# 15_IO_USB.net
KiCad netlist of a schematic drawn in Altium Designer
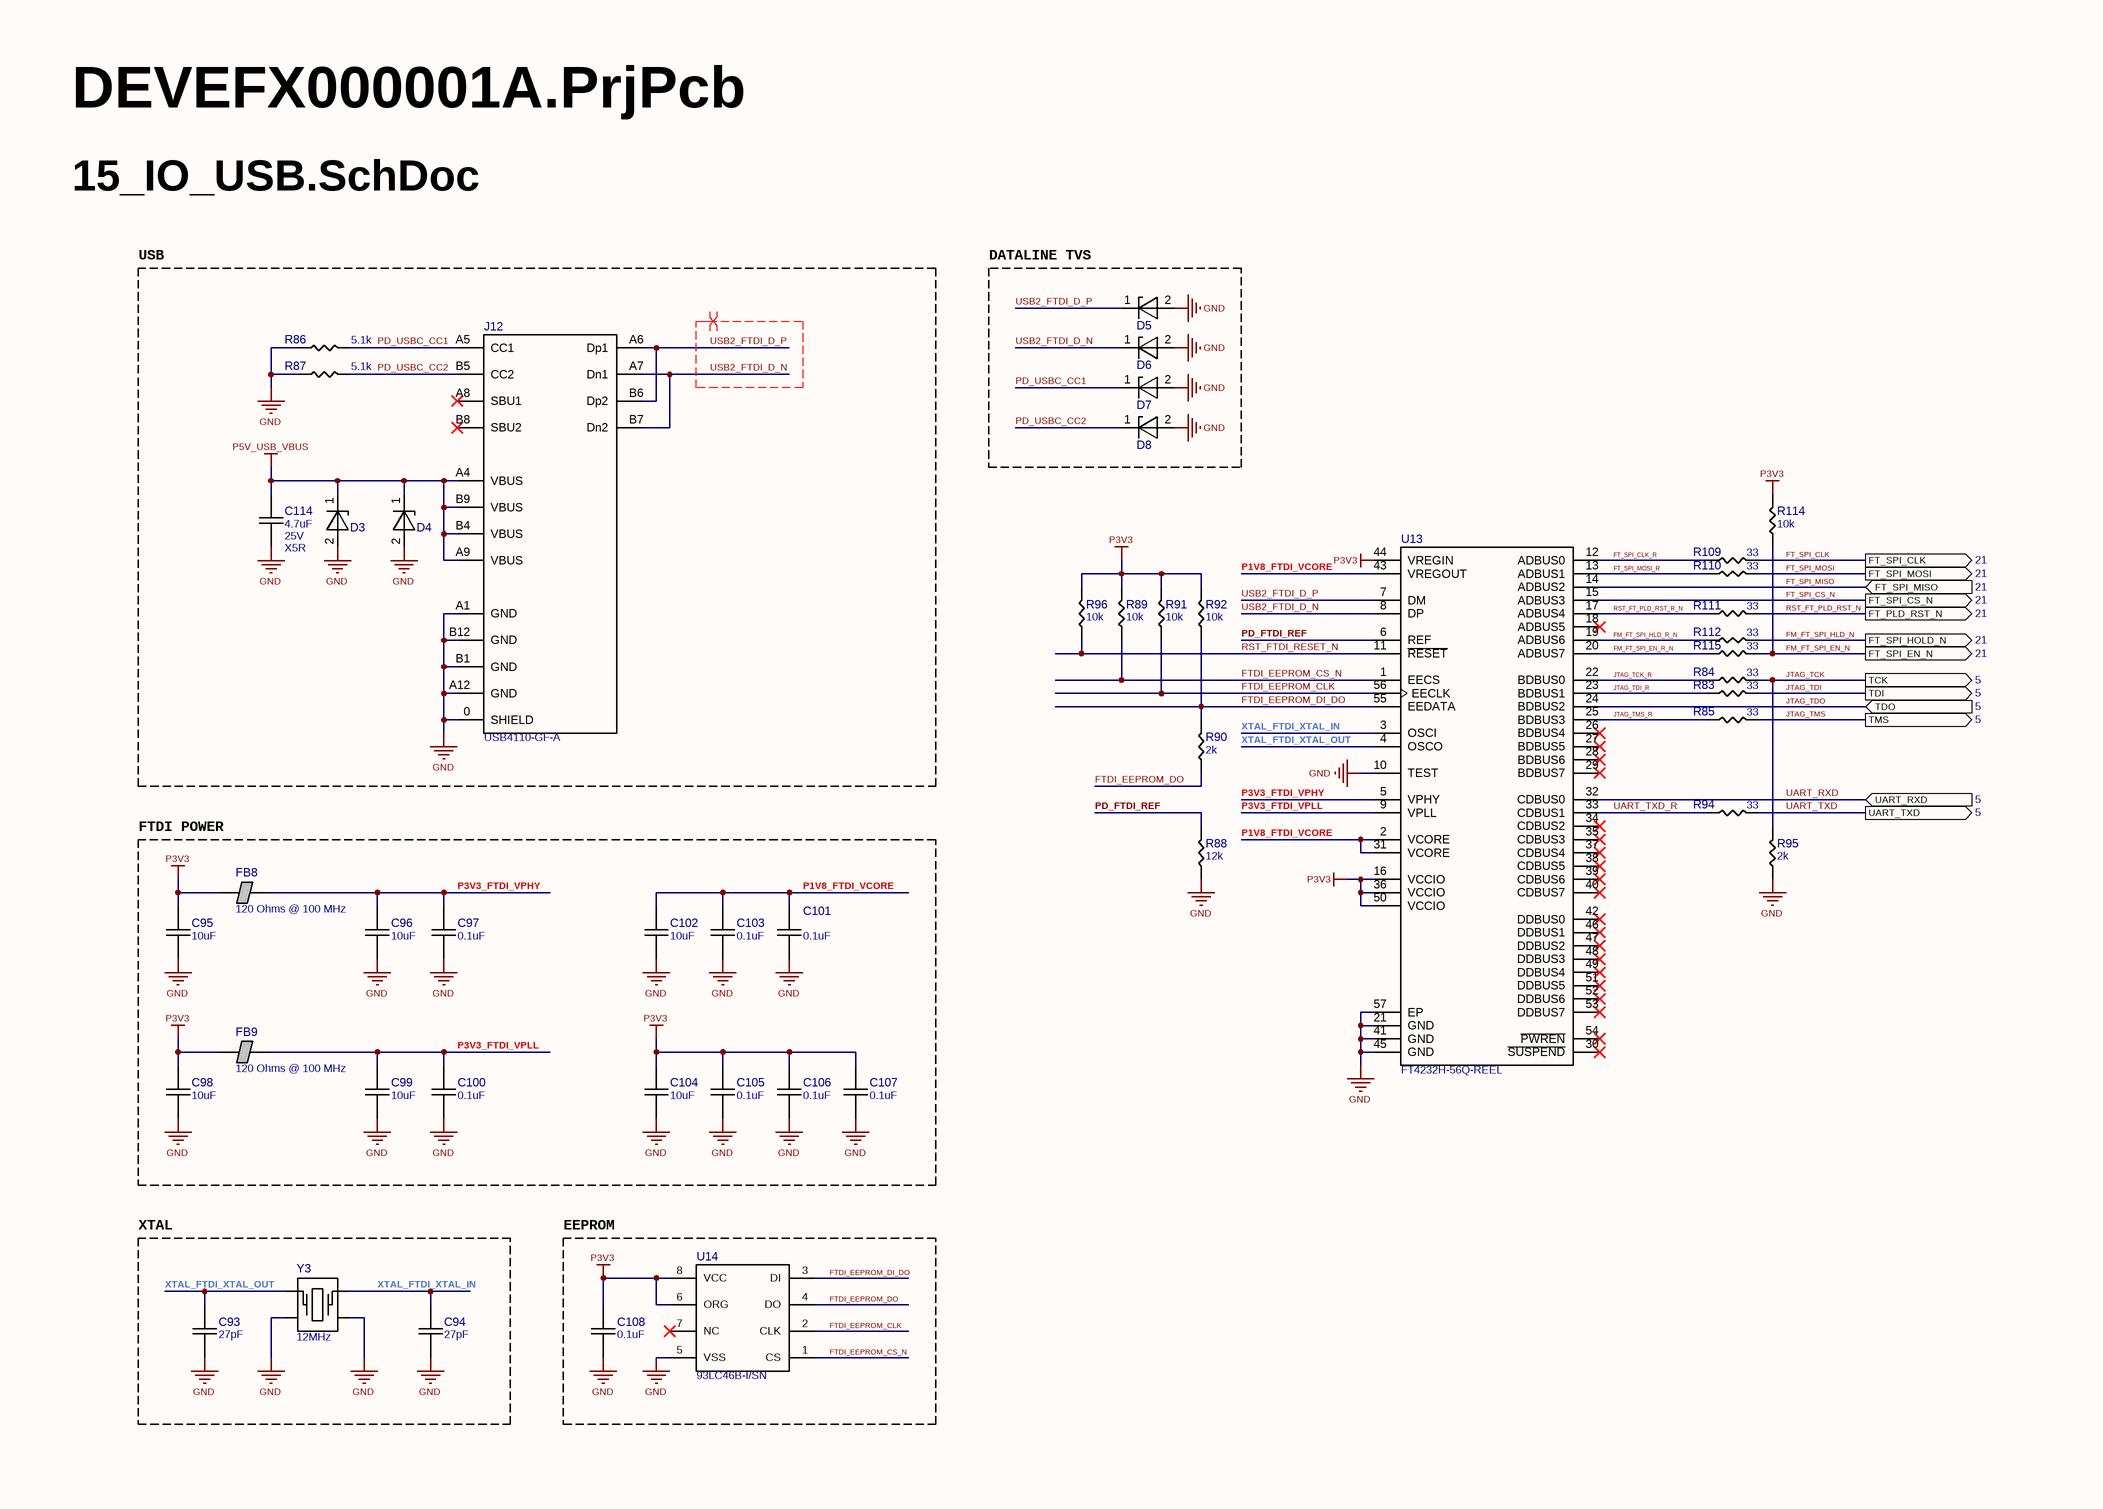
[diagram p0: 15_IO_USB.SchDoc]

(export (version "E")
  (design (tool "Eeschema 10.0.6"))
  (components
    (comp (ref "C93")
      (value "27pF")
      (footprint "CAPC1005X06N")
      (description "CAP CER 27PF 50V C0G/NPO 0402")
      (fields (field (name "PART NUMBER") "CC0402JRNPO9BN270") (field (name "VOLTAGE") "50V"))
      (libsource (lib "Database") (part "Capacitor"))
    )
    (comp (ref "C94")
      (value "27pF")
      (footprint "CAPC1005X06N")
      (description "CAP CER 27PF 50V C0G/NPO 0402")
      (fields (field (name "PART NUMBER") "CC0402JRNPO9BN270") (field (name "VOLTAGE") "50V"))
      (libsource (lib "Database") (part "Capacitor"))
    )
    (comp (ref "C95")
      (value "10uF")
      (footprint "CAPC1005X06N")
      (description "CAP CER 10UF 6.3V X5R 0402")
      (fields (field (name "PART NUMBER") "GRM155R60J106ME47D") (field (name "VOLTAGE") "6.3V"))
      (libsource (lib "Database") (part "Capacitor"))
    )
    (comp (ref "C96")
      (value "10uF")
      (footprint "CAPC1005X06N")
      (description "CAP CER 10UF 6.3V X5R 0402")
      (fields (field (name "PART NUMBER") "GRM155R60J106ME47D") (field (name "VOLTAGE") "6.3V"))
      (libsource (lib "Database") (part "Capacitor"))
    )
    (comp (ref "C97")
      (value "0.1uF")
      (footprint "CAPC1005X06N")
      (description "CAP CER 0.1UF 25V X7R 0402")
      (fields (field (name "PART NUMBER") "GRM155R71E104KE14J") (field (name "VOLTAGE") "25V"))
      (libsource (lib "Database") (part "Capacitor"))
    )
    (comp (ref "C98")
      (value "10uF")
      (footprint "CAPC1005X06N")
      (description "CAP CER 10UF 6.3V X5R 0402")
      (fields (field (name "PART NUMBER") "GRM155R60J106ME47D") (field (name "VOLTAGE") "6.3V"))
      (libsource (lib "Database") (part "Capacitor"))
    )
    (comp (ref "C99")
      (value "10uF")
      (footprint "CAPC1005X06N")
      (description "CAP CER 10UF 6.3V X5R 0402")
      (fields (field (name "PART NUMBER") "GRM155R60J106ME47D") (field (name "VOLTAGE") "6.3V"))
      (libsource (lib "Database") (part "Capacitor"))
    )
    (comp (ref "C100")
      (value "0.1uF")
      (footprint "CAPC1005X06N")
      (description "CAP CER 0.1UF 25V X7R 0402")
      (fields (field (name "PART NUMBER") "GRM155R71E104KE14J") (field (name "VOLTAGE") "25V"))
      (libsource (lib "Database") (part "Capacitor"))
    )
    (comp (ref "C101")
      (value "0.1uF")
      (footprint "CAPC1005X06N")
      (description "CAP CER 0.1UF 25V X7R 0402")
      (fields (field (name "PART NUMBER") "GRM155R71E104KE14J") (field (name "VOLTAGE") "25V"))
      (libsource (lib "Database") (part "Capacitor"))
    )
    (comp (ref "C102")
      (value "10uF")
      (footprint "CAPC1005X06N")
      (description "CAP CER 10UF 6.3V X5R 0402")
      (fields (field (name "PART NUMBER") "GRM155R60J106ME47D") (field (name "VOLTAGE") "6.3V"))
      (libsource (lib "Database") (part "Capacitor"))
    )
    (comp (ref "C103")
      (value "0.1uF")
      (footprint "CAPC1005X06N")
      (description "CAP CER 0.1UF 25V X7R 0402")
      (fields (field (name "PART NUMBER") "GRM155R71E104KE14J") (field (name "VOLTAGE") "25V"))
      (libsource (lib "Database") (part "Capacitor"))
    )
    (comp (ref "C104")
      (value "10uF")
      (footprint "CAPC1005X06N")
      (description "CAP CER 10UF 6.3V X5R 0402")
      (fields (field (name "PART NUMBER") "GRM155R60J106ME47D") (field (name "VOLTAGE") "6.3V"))
      (libsource (lib "Database") (part "Capacitor"))
    )
    (comp (ref "C105")
      (value "0.1uF")
      (footprint "CAPC1005X06N")
      (description "CAP CER 0.1UF 25V X7R 0402")
      (fields (field (name "PART NUMBER") "GRM155R71E104KE14J") (field (name "VOLTAGE") "25V"))
      (libsource (lib "Database") (part "Capacitor"))
    )
    (comp (ref "C106")
      (value "0.1uF")
      (footprint "CAPC1005X06N")
      (description "CAP CER 0.1UF 25V X7R 0402")
      (fields (field (name "PART NUMBER") "GRM155R71E104KE14J") (field (name "VOLTAGE") "25V"))
      (libsource (lib "Database") (part "Capacitor"))
    )
    (comp (ref "C107")
      (value "0.1uF")
      (footprint "CAPC1005X06N")
      (description "CAP CER 0.1UF 25V X7R 0402")
      (fields (field (name "PART NUMBER") "GRM155R71E104KE14J") (field (name "VOLTAGE") "25V"))
      (libsource (lib "Database") (part "Capacitor"))
    )
    (comp (ref "C108")
      (value "0.1uF")
      (footprint "CAPC1005X06N")
      (description "CAP CER 0.1UF 25V X7R 0402")
      (fields (field (name "PART NUMBER") "GRM155R71E104KE14J") (field (name "VOLTAGE") "25V"))
      (libsource (lib "Database") (part "Capacitor"))
    )
    (comp (ref "C114")
      (value "4.7uF")
      (footprint "CAPC1608X08N")
      (description "CAP CER 4.7UF 25V X5R 0603")
      (fields
        (field (name "PART NUMBER") "GRM188R61E475KE11D")
        (field (name "VOLTAGE") "25V")
        (field (name "TEMPC") "X5R")
      )
      (libsource (lib "Database") (part "Capacitor"))
    )
    (comp (ref "D3")
      (value "ESD401DPYR")
      (footprint "DFN65P100X50-2N")
      (description "TVS DIODE 5.5V 24V 2X1SON")
      (libsource (lib "Database") (part "Diode Zener"))
    )
    (comp (ref "D4")
      (value "ESD401DPYR")
      (footprint "DFN65P100X50-2N")
      (description "TVS DIODE 5.5V 24V 2X1SON")
      (libsource (lib "Database") (part "Diode Zener"))
    )
    (comp (ref "D5")
      (value "ESD401DPYR")
      (footprint "DFN65P100X50-2N")
      (description "TVS DIODE 5.5V 24V 2X1SON")
      (libsource (lib "Database") (part "Diode Zener"))
    )
    (comp (ref "D6")
      (value "ESD401DPYR")
      (footprint "DFN65P100X50-2N")
      (description "TVS DIODE 5.5V 24V 2X1SON")
      (libsource (lib "Database") (part "Diode Zener"))
    )
    (comp (ref "D7")
      (value "ESD401DPYR")
      (footprint "DFN65P100X50-2N")
      (description "TVS DIODE 5.5V 24V 2X1SON")
      (libsource (lib "Database") (part "Diode Zener"))
    )
    (comp (ref "D8")
      (value "ESD401DPYR")
      (footprint "DFN65P100X50-2N")
      (description "TVS DIODE 5.5V 24V 2X1SON")
      (libsource (lib "Database") (part "Diode Zener"))
    )
    (comp (ref "FB8")
      (value "120 Ohms @ 100 MHz")
      (footprint "INDC1005X05N")
      (description "FERRITE BEAD 120 OHM 0402 1LN")
      (fields (field (name "PART NUMBER") "BLM15PD121SN1D"))
      (libsource (lib "Database") (part "Bead"))
    )
    (comp (ref "FB9")
      (value "120 Ohms @ 100 MHz")
      (footprint "INDC1005X05N")
      (description "FERRITE BEAD 120 OHM 0402 1LN")
      (fields (field (name "PART NUMBER") "BLM15PD121SN1D"))
      (libsource (lib "Database") (part "Bead"))
    )
    (comp (ref "J12")
      (value "USB4110-GF-A")
      (footprint "GCT_USB4110-GF-A")
      (description "CONN RCP USB2.0 TYP C 24P SMD RA")
      (libsource (lib "Database") (part "Connector Type-C USB2"))
    )
    (comp (ref "R83")
      (value "33")
      (footprint "RESC1005X03N")
      (description "RES SMD 33 OHM 1% 1/16W 0402")
      (fields (field (name "PART NUMBER") "RC0402FR-0733RL"))
      (libsource (lib "Database") (part "Resistor_ENG"))
    )
    (comp (ref "R84")
      (value "33")
      (footprint "RESC1005X03N")
      (description "RES SMD 33 OHM 1% 1/16W 0402")
      (fields (field (name "PART NUMBER") "RC0402FR-0733RL"))
      (libsource (lib "Database") (part "Resistor_ENG"))
    )
    (comp (ref "R85")
      (value "33")
      (footprint "RESC1005X03N")
      (description "RES SMD 33 OHM 1% 1/16W 0402")
      (fields (field (name "PART NUMBER") "RC0402FR-0733RL"))
      (libsource (lib "Database") (part "Resistor_ENG"))
    )
    (comp (ref "R86")
      (value "5.1k")
      (footprint "RESC1005X03N")
      (description "RES SMD 5.1K OHM 1% 1/16W 0402")
      (fields (field (name "PART NUMBER") "RC0402FR-075K1L"))
      (libsource (lib "Database") (part "Resistor_ENG"))
    )
    (comp (ref "R87")
      (value "5.1k")
      (footprint "RESC1005X03N")
      (description "RES SMD 5.1K OHM 1% 1/16W 0402")
      (fields (field (name "PART NUMBER") "RC0402FR-075K1L"))
      (libsource (lib "Database") (part "Resistor_ENG"))
    )
    (comp (ref "R88")
      (value "12k")
      (footprint "RESC1005X03N")
      (description "RES SMD 12K OHM 1% 1/16W 0402")
      (fields (field (name "PART NUMBER") "RC0402FR-0712KL"))
      (libsource (lib "Database") (part "Resistor_ENG"))
    )
    (comp (ref "R89")
      (value "10k")
      (footprint "RESC1005X03N")
      (description "RES SMD 10K OHM 1% 1/16W 0402")
      (fields (field (name "PART NUMBER") "RC0402FR-0710KL"))
      (libsource (lib "Database") (part "Resistor_ENG"))
    )
    (comp (ref "R90")
      (value "2k")
      (footprint "RESC1005X03N")
      (description "RES SMD 2K OHM 1% 1/16W 0402")
      (fields (field (name "PART NUMBER") "RC0402FR-072KL"))
      (libsource (lib "Database") (part "Resistor_ENG"))
    )
    (comp (ref "R91")
      (value "10k")
      (footprint "RESC1005X03N")
      (description "RES SMD 10K OHM 1% 1/16W 0402")
      (fields (field (name "PART NUMBER") "RC0402FR-0710KL"))
      (libsource (lib "Database") (part "Resistor_ENG"))
    )
    (comp (ref "R92")
      (value "10k")
      (footprint "RESC1005X03N")
      (description "RES SMD 10K OHM 1% 1/16W 0402")
      (fields (field (name "PART NUMBER") "RC0402FR-0710KL"))
      (libsource (lib "Database") (part "Resistor_ENG"))
    )
    (comp (ref "R94")
      (value "33")
      (footprint "RESC1005X03N")
      (description "RES SMD 33 OHM 1% 1/16W 0402")
      (fields (field (name "PART NUMBER") "RC0402FR-0733RL"))
      (libsource (lib "Database") (part "Resistor_ENG"))
    )
    (comp (ref "R95")
      (value "2k")
      (footprint "RESC1005X03N")
      (description "RES SMD 2K OHM 1% 1/16W 0402")
      (fields (field (name "PART NUMBER") "RC0402FR-072KL"))
      (libsource (lib "Database") (part "Resistor_ENG"))
    )
    (comp (ref "R96")
      (value "10k")
      (footprint "RESC1005X03N")
      (description "RES SMD 10K OHM 1% 1/16W 0402")
      (fields (field (name "PART NUMBER") "RC0402FR-0710KL"))
      (libsource (lib "Database") (part "Resistor_ENG"))
    )
    (comp (ref "R109")
      (value "33")
      (footprint "RESC1005X03N")
      (description "RES SMD 33 OHM 1% 1/16W 0402")
      (fields (field (name "PART NUMBER") "RC0402FR-0733RL"))
      (libsource (lib "Database") (part "Resistor_ENG"))
    )
    (comp (ref "R110")
      (value "33")
      (footprint "RESC1005X03N")
      (description "RES SMD 33 OHM 1% 1/16W 0402")
      (fields (field (name "PART NUMBER") "RC0402FR-0733RL"))
      (libsource (lib "Database") (part "Resistor_ENG"))
    )
    (comp (ref "R111")
      (value "33")
      (footprint "RESC1005X03N")
      (description "RES SMD 33 OHM 1% 1/16W 0402")
      (fields (field (name "PART NUMBER") "RC0402FR-0733RL"))
      (libsource (lib "Database") (part "Resistor_ENG"))
    )
    (comp (ref "R112")
      (value "33")
      (footprint "RESC1005X03N")
      (description "RES SMD 33 OHM 1% 1/16W 0402")
      (fields (field (name "PART NUMBER") "RC0402FR-0733RL"))
      (libsource (lib "Database") (part "Resistor_ENG"))
    )
    (comp (ref "R114")
      (value "10k")
      (footprint "RESC1005X03N")
      (description "RES SMD 10K OHM 1% 1/16W 0402")
      (fields (field (name "PART NUMBER") "RC0402FR-0710KL"))
      (libsource (lib "Database") (part "Resistor_ENG"))
    )
    (comp (ref "R115")
      (value "33")
      (footprint "RESC1005X03N")
      (description "RES SMD 33 OHM 1% 1/16W 0402")
      (fields (field (name "PART NUMBER") "RC0402FR-0733RL"))
      (libsource (lib "Database") (part "Resistor_ENG"))
    )
    (comp (ref "U13")
      (value "FT4232H-56Q-REEL")
      (footprint "QFN50P800X800X90_HS-57N")
      (description "IC USB TO UART/MPSSE QUAD 56VQFN")
      (libsource (lib "Database") (part "FT4232H-56Q"))
    )
    (comp (ref "U14")
      (value "93LC46B-I/SN")
      (footprint "SOIC127P590X175-8N")
      (description "IC EEPROM 1KBIT SPI 2MHZ 8SOIC")
      (libsource (lib "Database") (part "SO-8 EEPROM"))
    )
    (comp (ref "Y3")
      (value "12MHz")
      (footprint "XTAL_3225")
      (description "CRYSTAL 12.0000MHZ 18PF SMD")
      (fields (field (name "PART NUMBER") "7V-12.000MDDJ-T"))
      (libsource (lib "Database") (part "Crystal_1"))
    )
  )
  (nets
    (net (code "1") (name "/FM_FT_SPI_EN_N") (class "Default")
      (node (ref "R114") (pin "1") (pinfunction "1_1") (pintype "passive"))
      (node (ref "R115") (pin "2") (pinfunction "2_2") (pintype "passive"))
    )
    (net (code "2") (name "/FM_FT_SPI_EN_R_N") (class "Default")
      (node (ref "R115") (pin "1") (pinfunction "1_1") (pintype "passive"))
      (node (ref "U13") (pin "20") (pinfunction "ADBUS7_20") (pintype "passive"))
    )
    (net (code "3") (name "/FM_FT_SPI_HLD_N") (class "Default")
      (node (ref "R112") (pin "2") (pinfunction "2_2") (pintype "passive"))
    )
    (net (code "4") (name "/FM_FT_SPI_HLD_R_N") (class "Default")
      (node (ref "R112") (pin "1") (pinfunction "1_1") (pintype "passive"))
      (node (ref "U13") (pin "19") (pinfunction "ADBUS6_19") (pintype "passive"))
    )
    (net (code "5") (name "/FTDI_EEPROM_CLK") (class "Default")
      (node (ref "R91") (pin "1") (pinfunction "1_1") (pintype "passive"))
      (node (ref "U13") (pin "56") (pinfunction "EECLK_56") (pintype "passive"))
      (node (ref "U14") (pin "2") (pinfunction "CLK_2") (pintype "passive"))
    )
    (net (code "6") (name "/FTDI_EEPROM_CS_N") (class "Default")
      (node (ref "R89") (pin "1") (pinfunction "1_1") (pintype "passive"))
      (node (ref "U13") (pin "1") (pinfunction "EECS_1") (pintype "passive"))
      (node (ref "U14") (pin "1") (pinfunction "CS_1") (pintype "passive"))
    )
    (net (code "7") (name "/FTDI_EEPROM_DI_DO") (class "Default")
      (node (ref "R90") (pin "2") (pinfunction "2_2") (pintype "passive"))
      (node (ref "R92") (pin "1") (pinfunction "1_1") (pintype "passive"))
      (node (ref "U13") (pin "55") (pinfunction "EEDATA_55") (pintype "passive"))
      (node (ref "U14") (pin "3") (pinfunction "DI_3") (pintype "passive"))
    )
    (net (code "8") (name "/FTDI_EEPROM_DO") (class "Default")
      (node (ref "R90") (pin "1") (pinfunction "1_1") (pintype "passive"))
      (node (ref "U14") (pin "4") (pinfunction "DO_4") (pintype "passive"))
    )
    (net (code "9") (name "/FT_SPI_CLK") (class "Default")
      (node (ref "R109") (pin "2") (pinfunction "2_2") (pintype "passive"))
    )
    (net (code "10") (name "/FT_SPI_CLK_R") (class "Default")
      (node (ref "R109") (pin "1") (pinfunction "1_1") (pintype "passive"))
      (node (ref "U13") (pin "12") (pinfunction "ADBUS0_12") (pintype "passive"))
    )
    (net (code "11") (name "/FT_SPI_CS_N") (class "Default")
      (node (ref "U13") (pin "15") (pinfunction "ADBUS3_15") (pintype "passive"))
    )
    (net (code "12") (name "/FT_SPI_MISO") (class "Default")
      (node (ref "U13") (pin "14") (pinfunction "ADBUS2_14") (pintype "passive"))
    )
    (net (code "13") (name "/FT_SPI_MOSI") (class "Default")
      (node (ref "R110") (pin "2") (pinfunction "2_2") (pintype "passive"))
    )
    (net (code "14") (name "/FT_SPI_MOSI_R") (class "Default")
      (node (ref "R110") (pin "1") (pinfunction "1_1") (pintype "passive"))
      (node (ref "U13") (pin "13") (pinfunction "ADBUS1_13") (pintype "passive"))
    )
    (net (code "15") (name "/JTAG_TCK") (class "Default")
      (node (ref "R84") (pin "2") (pinfunction "2_2") (pintype "passive"))
      (node (ref "R95") (pin "2") (pinfunction "2_2") (pintype "passive"))
    )
    (net (code "16") (name "/JTAG_TCK_R") (class "Default")
      (node (ref "R84") (pin "1") (pinfunction "1_1") (pintype "passive"))
      (node (ref "U13") (pin "22") (pinfunction "BDBUS0_22") (pintype "passive"))
    )
    (net (code "17") (name "/JTAG_TDI") (class "Default")
      (node (ref "R83") (pin "2") (pinfunction "2_2") (pintype "passive"))
    )
    (net (code "18") (name "/JTAG_TDI_R") (class "Default")
      (node (ref "R83") (pin "1") (pinfunction "1_1") (pintype "passive"))
      (node (ref "U13") (pin "23") (pinfunction "BDBUS1_23") (pintype "passive"))
    )
    (net (code "19") (name "/JTAG_TDO") (class "Default")
      (node (ref "U13") (pin "24") (pinfunction "BDBUS2_24") (pintype "passive"))
    )
    (net (code "20") (name "/JTAG_TMS") (class "Default")
      (node (ref "R85") (pin "2") (pinfunction "2_2") (pintype "passive"))
    )
    (net (code "21") (name "/JTAG_TMS_R") (class "Default")
      (node (ref "R85") (pin "1") (pinfunction "1_1") (pintype "passive"))
      (node (ref "U13") (pin "25") (pinfunction "BDBUS3_25") (pintype "passive"))
    )
    (net (code "22") (name "/P1V8_FTDI_VCORE") (class "Default")
      (node (ref "C101") (pin "2") (pinfunction "2_2") (pintype "passive"))
      (node (ref "C102") (pin "2") (pinfunction "2_2") (pintype "passive"))
      (node (ref "C103") (pin "2") (pinfunction "2_2") (pintype "passive"))
      (node (ref "U13") (pin "2") (pinfunction "VCORE_2") (pintype "passive"))
      (node (ref "U13") (pin "31") (pinfunction "VCORE_31") (pintype "passive"))
      (node (ref "U13") (pin "43") (pinfunction "VREGOUT_43") (pintype "passive"))
    )
    (net (code "23") (name "/P3V3_FTDI_VPHY") (class "Default")
      (node (ref "C96") (pin "2") (pinfunction "2_2") (pintype "passive"))
      (node (ref "C97") (pin "2") (pinfunction "2_2") (pintype "passive"))
      (node (ref "FB8") (pin "2") (pinfunction "2_2") (pintype "passive"))
      (node (ref "U13") (pin "5") (pinfunction "VPHY_5") (pintype "passive"))
    )
    (net (code "24") (name "/P3V3_FTDI_VPLL") (class "Default")
      (node (ref "C100") (pin "2") (pinfunction "2_2") (pintype "passive"))
      (node (ref "C99") (pin "2") (pinfunction "2_2") (pintype "passive"))
      (node (ref "FB9") (pin "2") (pinfunction "2_2") (pintype "passive"))
      (node (ref "U13") (pin "9") (pinfunction "VPLL_9") (pintype "passive"))
    )
    (net (code "25") (name "/PD_FTDI_REF") (class "Default")
      (node (ref "R88") (pin "2") (pinfunction "2_2") (pintype "passive"))
      (node (ref "U13") (pin "6") (pinfunction "REF_6") (pintype "passive"))
    )
    (net (code "26") (name "/PD_USBC_CC1") (class "Default")
      (node (ref "D7") (pin "1") (pinfunction "C_1") (pintype "passive"))
      (node (ref "J12") (pin "A5") (pinfunction "CC1_A5") (pintype "passive"))
      (node (ref "R86") (pin "2") (pinfunction "2_2") (pintype "passive"))
    )
    (net (code "27") (name "/PD_USBC_CC2") (class "Default")
      (node (ref "D8") (pin "1") (pinfunction "C_1") (pintype "passive"))
      (node (ref "J12") (pin "B5") (pinfunction "CC2_B5") (pintype "passive"))
      (node (ref "R87") (pin "2") (pinfunction "2_2") (pintype "passive"))
    )
    (net (code "28") (name "/RST_FTDI_RESET_N") (class "Default")
      (node (ref "R96") (pin "1") (pinfunction "1_1") (pintype "passive"))
      (node (ref "U13") (pin "11") (pinfunction "~{RESET}_11") (pintype "passive"))
    )
    (net (code "29") (name "/RST_FT_PLD_RST_N") (class "Default")
      (node (ref "R111") (pin "2") (pinfunction "2_2") (pintype "passive"))
    )
    (net (code "30") (name "/RST_FT_PLD_RST_R_N") (class "Default")
      (node (ref "R111") (pin "1") (pinfunction "1_1") (pintype "passive"))
      (node (ref "U13") (pin "17") (pinfunction "ADBUS4_17") (pintype "passive"))
    )
    (net (code "31") (name "/UART_RXD") (class "Default")
      (node (ref "U13") (pin "32") (pinfunction "CDBUS0_32") (pintype "passive"))
    )
    (net (code "32") (name "/UART_TXD") (class "Default")
      (node (ref "R94") (pin "2") (pinfunction "2_2") (pintype "passive"))
    )
    (net (code "33") (name "/UART_TXD_R") (class "Default")
      (node (ref "R94") (pin "1") (pinfunction "1_1") (pintype "passive"))
      (node (ref "U13") (pin "33") (pinfunction "CDBUS1_33") (pintype "passive"))
    )
    (net (code "34") (name "/USB2_FTDI_D_N") (class "Default")
      (node (ref "D6") (pin "1") (pinfunction "C_1") (pintype "passive"))
      (node (ref "J12") (pin "A7") (pinfunction "Dn1_A7") (pintype "passive"))
      (node (ref "J12") (pin "B7") (pinfunction "Dn2_B7") (pintype "passive"))
      (node (ref "U13") (pin "8") (pinfunction "DP_8") (pintype "passive"))
    )
    (net (code "35") (name "/USB2_FTDI_D_P") (class "Default")
      (node (ref "D5") (pin "1") (pinfunction "C_1") (pintype "passive"))
      (node (ref "J12") (pin "A6") (pinfunction "Dp1_A6") (pintype "passive"))
      (node (ref "J12") (pin "B6") (pinfunction "Dp2_B6") (pintype "passive"))
      (node (ref "U13") (pin "7") (pinfunction "DM_7") (pintype "passive"))
    )
    (net (code "36") (name "/XTAL_FTDI_XTAL_IN") (class "Default")
      (node (ref "C94") (pin "2") (pinfunction "2_2") (pintype "passive"))
      (node (ref "U13") (pin "3") (pinfunction "OSCI_3") (pintype "passive"))
      (node (ref "Y3") (pin "3") (pinfunction "3_3") (pintype "passive"))
    )
    (net (code "37") (name "/XTAL_FTDI_XTAL_OUT") (class "Default")
      (node (ref "C93") (pin "2") (pinfunction "2_2") (pintype "passive"))
      (node (ref "U13") (pin "4") (pinfunction "OSCO_4") (pintype "passive"))
      (node (ref "Y3") (pin "1") (pinfunction "1_1") (pintype "passive"))
    )
    (net (code "38") (name "GND") (class "Default")
      (node (ref "C100") (pin "1") (pinfunction "1_1") (pintype "passive"))
      (node (ref "C101") (pin "1") (pinfunction "1_1") (pintype "passive"))
      (node (ref "C102") (pin "1") (pinfunction "1_1") (pintype "passive"))
      (node (ref "C103") (pin "1") (pinfunction "1_1") (pintype "passive"))
      (node (ref "C104") (pin "1") (pinfunction "1_1") (pintype "passive"))
      (node (ref "C105") (pin "1") (pinfunction "1_1") (pintype "passive"))
      (node (ref "C106") (pin "1") (pinfunction "1_1") (pintype "passive"))
      (node (ref "C107") (pin "1") (pinfunction "1_1") (pintype "passive"))
      (node (ref "C108") (pin "1") (pinfunction "1_1") (pintype "passive"))
      (node (ref "C114") (pin "1") (pinfunction "1_1") (pintype "passive"))
      (node (ref "C93") (pin "1") (pinfunction "1_1") (pintype "passive"))
      (node (ref "C94") (pin "1") (pinfunction "1_1") (pintype "passive"))
      (node (ref "C95") (pin "1") (pinfunction "1_1") (pintype "passive"))
      (node (ref "C96") (pin "1") (pinfunction "1_1") (pintype "passive"))
      (node (ref "C97") (pin "1") (pinfunction "1_1") (pintype "passive"))
      (node (ref "C98") (pin "1") (pinfunction "1_1") (pintype "passive"))
      (node (ref "C99") (pin "1") (pinfunction "1_1") (pintype "passive"))
      (node (ref "D3") (pin "2") (pinfunction "A_2") (pintype "passive"))
      (node (ref "D4") (pin "2") (pinfunction "A_2") (pintype "passive"))
      (node (ref "D5") (pin "2") (pinfunction "A_2") (pintype "passive"))
      (node (ref "D6") (pin "2") (pinfunction "A_2") (pintype "passive"))
      (node (ref "D7") (pin "2") (pinfunction "A_2") (pintype "passive"))
      (node (ref "D8") (pin "2") (pinfunction "A_2") (pintype "passive"))
      (node (ref "J12") (pin "0") (pinfunction "SHIELD_0") (pintype "passive"))
      (node (ref "J12") (pin "A1") (pinfunction "GND_A1") (pintype "passive"))
      (node (ref "J12") (pin "A12") (pinfunction "GND_A12") (pintype "passive"))
      (node (ref "J12") (pin "B1") (pinfunction "GND_B1") (pintype "passive"))
      (node (ref "J12") (pin "B12") (pinfunction "GND_B12") (pintype "passive"))
      (node (ref "R86") (pin "1") (pinfunction "1_1") (pintype "passive"))
      (node (ref "R87") (pin "1") (pinfunction "1_1") (pintype "passive"))
      (node (ref "R88") (pin "1") (pinfunction "1_1") (pintype "passive"))
      (node (ref "R95") (pin "1") (pinfunction "1_1") (pintype "passive"))
      (node (ref "U13") (pin "10") (pinfunction "TEST_10") (pintype "passive"))
      (node (ref "U13") (pin "21") (pinfunction "GND_21") (pintype "passive"))
      (node (ref "U13") (pin "41") (pinfunction "GND_41") (pintype "passive"))
      (node (ref "U13") (pin "45") (pinfunction "GND_45") (pintype "passive"))
      (node (ref "U13") (pin "57") (pinfunction "EP_57") (pintype "passive"))
      (node (ref "U14") (pin "5") (pinfunction "VSS_5") (pintype "passive"))
      (node (ref "Y3") (pin "2") (pinfunction "2_2") (pintype "passive"))
      (node (ref "Y3") (pin "4") (pinfunction "4_4") (pintype "passive"))
    )
    (net (code "39") (name "P3V3") (class "Default")
      (node (ref "C104") (pin "2") (pinfunction "2_2") (pintype "passive"))
      (node (ref "C105") (pin "2") (pinfunction "2_2") (pintype "passive"))
      (node (ref "C106") (pin "2") (pinfunction "2_2") (pintype "passive"))
      (node (ref "C107") (pin "2") (pinfunction "2_2") (pintype "passive"))
      (node (ref "C108") (pin "2") (pinfunction "2_2") (pintype "passive"))
      (node (ref "C95") (pin "2") (pinfunction "2_2") (pintype "passive"))
      (node (ref "C98") (pin "2") (pinfunction "2_2") (pintype "passive"))
      (node (ref "FB8") (pin "1") (pinfunction "1_1") (pintype "passive"))
      (node (ref "FB9") (pin "1") (pinfunction "1_1") (pintype "passive"))
      (node (ref "R114") (pin "2") (pinfunction "2_2") (pintype "passive"))
      (node (ref "R89") (pin "2") (pinfunction "2_2") (pintype "passive"))
      (node (ref "R91") (pin "2") (pinfunction "2_2") (pintype "passive"))
      (node (ref "R92") (pin "2") (pinfunction "2_2") (pintype "passive"))
      (node (ref "R96") (pin "2") (pinfunction "2_2") (pintype "passive"))
      (node (ref "U13") (pin "16") (pinfunction "VCCIO_16") (pintype "passive"))
      (node (ref "U13") (pin "36") (pinfunction "VCCIO_36") (pintype "passive"))
      (node (ref "U13") (pin "44") (pinfunction "VREGIN_44") (pintype "passive"))
      (node (ref "U13") (pin "50") (pinfunction "VCCIO_50") (pintype "passive"))
      (node (ref "U14") (pin "6") (pinfunction "ORG_6") (pintype "passive"))
      (node (ref "U14") (pin "8") (pinfunction "VCC_8") (pintype "passive"))
    )
    (net (code "40") (name "P5V_USB_VBUS") (class "Default")
      (node (ref "C114") (pin "2") (pinfunction "2_2") (pintype "passive"))
      (node (ref "D3") (pin "1") (pinfunction "C_1") (pintype "passive"))
      (node (ref "D4") (pin "1") (pinfunction "C_1") (pintype "passive"))
      (node (ref "J12") (pin "A4") (pinfunction "VBUS_A4") (pintype "passive"))
      (node (ref "J12") (pin "A9") (pinfunction "VBUS_A9") (pintype "passive"))
      (node (ref "J12") (pin "B4") (pinfunction "VBUS_B4") (pintype "passive"))
      (node (ref "J12") (pin "B9") (pinfunction "VBUS_B9") (pintype "passive"))
    )
    (net (code "41") (name "unconnected-(J12-SBU1-PadA8)") (class "Default")
      (node (ref "J12") (pin "A8") (pinfunction "SBU1_A8") (pintype "passive+no_connect"))
    )
    (net (code "42") (name "unconnected-(J12-SBU2-PadB8)") (class "Default")
      (node (ref "J12") (pin "B8") (pinfunction "SBU2_B8") (pintype "passive+no_connect"))
    )
    (net (code "43") (name "unconnected-(U13-ADBUS5-Pad18)") (class "Default")
      (node (ref "U13") (pin "18") (pinfunction "ADBUS5_18") (pintype "passive+no_connect"))
    )
    (net (code "44") (name "unconnected-(U13-BDBUS4-Pad26)") (class "Default")
      (node (ref "U13") (pin "26") (pinfunction "BDBUS4_26") (pintype "passive+no_connect"))
    )
    (net (code "45") (name "unconnected-(U13-BDBUS5-Pad27)") (class "Default")
      (node (ref "U13") (pin "27") (pinfunction "BDBUS5_27") (pintype "passive+no_connect"))
    )
    (net (code "46") (name "unconnected-(U13-BDBUS6-Pad28)") (class "Default")
      (node (ref "U13") (pin "28") (pinfunction "BDBUS6_28") (pintype "passive+no_connect"))
    )
    (net (code "47") (name "unconnected-(U13-BDBUS7-Pad29)") (class "Default")
      (node (ref "U13") (pin "29") (pinfunction "BDBUS7_29") (pintype "passive+no_connect"))
    )
    (net (code "48") (name "unconnected-(U13-CDBUS2-Pad34)") (class "Default")
      (node (ref "U13") (pin "34") (pinfunction "CDBUS2_34") (pintype "passive+no_connect"))
    )
    (net (code "49") (name "unconnected-(U13-CDBUS3-Pad35)") (class "Default")
      (node (ref "U13") (pin "35") (pinfunction "CDBUS3_35") (pintype "passive+no_connect"))
    )
    (net (code "50") (name "unconnected-(U13-CDBUS4-Pad37)") (class "Default")
      (node (ref "U13") (pin "37") (pinfunction "CDBUS4_37") (pintype "passive+no_connect"))
    )
    (net (code "51") (name "unconnected-(U13-CDBUS5-Pad38)") (class "Default")
      (node (ref "U13") (pin "38") (pinfunction "CDBUS5_38") (pintype "passive+no_connect"))
    )
    (net (code "52") (name "unconnected-(U13-CDBUS6-Pad39)") (class "Default")
      (node (ref "U13") (pin "39") (pinfunction "CDBUS6_39") (pintype "passive+no_connect"))
    )
    (net (code "53") (name "unconnected-(U13-CDBUS7-Pad40)") (class "Default")
      (node (ref "U13") (pin "40") (pinfunction "CDBUS7_40") (pintype "passive+no_connect"))
    )
    (net (code "54") (name "unconnected-(U13-DDBUS0-Pad42)") (class "Default")
      (node (ref "U13") (pin "42") (pinfunction "DDBUS0_42") (pintype "passive+no_connect"))
    )
    (net (code "55") (name "unconnected-(U13-DDBUS1-Pad46)") (class "Default")
      (node (ref "U13") (pin "46") (pinfunction "DDBUS1_46") (pintype "passive+no_connect"))
    )
    (net (code "56") (name "unconnected-(U13-DDBUS2-Pad47)") (class "Default")
      (node (ref "U13") (pin "47") (pinfunction "DDBUS2_47") (pintype "passive+no_connect"))
    )
    (net (code "57") (name "unconnected-(U13-DDBUS3-Pad48)") (class "Default")
      (node (ref "U13") (pin "48") (pinfunction "DDBUS3_48") (pintype "passive+no_connect"))
    )
    (net (code "58") (name "unconnected-(U13-DDBUS4-Pad49)") (class "Default")
      (node (ref "U13") (pin "49") (pinfunction "DDBUS4_49") (pintype "passive+no_connect"))
    )
    (net (code "59") (name "unconnected-(U13-DDBUS5-Pad51)") (class "Default")
      (node (ref "U13") (pin "51") (pinfunction "DDBUS5_51") (pintype "passive+no_connect"))
    )
    (net (code "60") (name "unconnected-(U13-DDBUS6-Pad52)") (class "Default")
      (node (ref "U13") (pin "52") (pinfunction "DDBUS6_52") (pintype "passive+no_connect"))
    )
    (net (code "61") (name "unconnected-(U13-DDBUS7-Pad53)") (class "Default")
      (node (ref "U13") (pin "53") (pinfunction "DDBUS7_53") (pintype "passive+no_connect"))
    )
    (net (code "62") (name "unconnected-(U13-~{PWREN}-Pad54)") (class "Default")
      (node (ref "U13") (pin "54") (pinfunction "~{PWREN}_54") (pintype "passive+no_connect"))
    )
    (net (code "63") (name "unconnected-(U13-~{SUSPEND}-Pad30)") (class "Default")
      (node (ref "U13") (pin "30") (pinfunction "~{SUSPEND}_30") (pintype "passive+no_connect"))
    )
    (net (code "64") (name "unconnected-(U14-NC-Pad7)") (class "Default")
      (node (ref "U14") (pin "7") (pinfunction "NC_7") (pintype "passive+no_connect"))
    )
  )
)
